# board.net
KiCad netlist of a schematic drawn in EAGLE
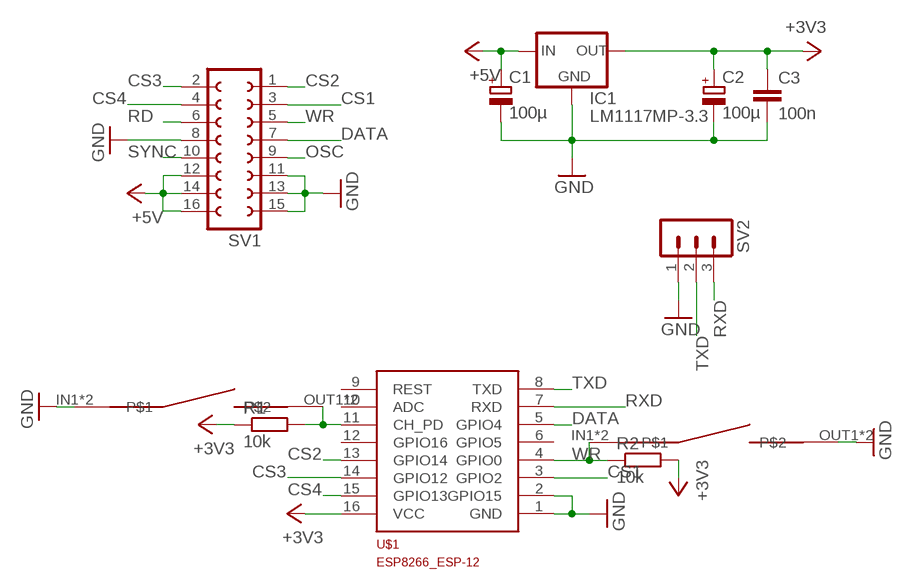
[diagram p0: schematic, sheet 1]

(export (version "E")
  (design (tool "Eeschema 10.0.6"))
  (components
    (comp (ref "C1")
      (value "100µ")
      (footprint "eagle-import:E2,5-6")
      (libsource (lib "eagle-import") (part "CPOL-EUE2.5-6"))
    )
    (comp (ref "C2")
      (value "100µ")
      (footprint "eagle-import:E2,5-6")
      (libsource (lib "eagle-import") (part "CPOL-EUE2.5-6"))
    )
    (comp (ref "C3")
      (value "100n")
      (footprint "eagle-import:C0805")
      (libsource (lib "eagle-import") (part "C-EUC0805"))
    )
    (comp (ref "IC1")
      (value "LM1117MP-3.3")
      (footprint "eagle-import:SOT223")
      (fields (field (name "MF") "Texas Instruments"))
      (libsource (lib "eagle-import") (part "LM1117?-MP3.3"))
    )
    (comp (ref "R1")
      (value "10k")
      (footprint "eagle-import:R0805")
      (libsource (lib "eagle-import") (part "R-EU_R0805"))
    )
    (comp (ref "R2")
      (value "10k")
      (footprint "eagle-import:R0805")
      (libsource (lib "eagle-import") (part "R-EU_R0805"))
    )
    (comp (ref "SV1")
      (value "FE08-2")
      (footprint "eagle-import:FE08-2")
      (libsource (lib "eagle-import") (part "FE08-2"))
    )
    (comp (ref "SV2")
      (value "MA03-1")
      (footprint "eagle-import:MA03-1")
      (libsource (lib "eagle-import") (part "MA03-1"))
    )
    (comp (ref "U$1")
      (value "ESP8266_ESP-12")
      (footprint "eagle-import:ESP8266-ESP12")
      (libsource (lib "eagle-import") (part "ESP8266_ESP-12"))
    )
    (comp (ref "U$2")
      (value "KMR221")
      (footprint "eagle-import:KMR221")
      (libsource (lib "eagle-import") (part "KMR221"))
    )
    (comp (ref "U$3")
      (value "KMR221")
      (footprint "eagle-import:KMR221")
      (libsource (lib "eagle-import") (part "KMR221"))
    )
  )
  (nets
    (net (code "1") (name "+3V3") (class "Default")
      (node (ref "C2") (pin "+") (pinfunction "+_+") (pintype "passive"))
      (node (ref "C3") (pin "1") (pinfunction "1_1") (pintype "passive"))
      (node (ref "IC1") (pin "2") (pinfunction "OUT_2") (pintype "passive"))
      (node (ref "IC1") (pin "4") (pinfunction "OUT_4") (pintype "passive"))
      (node (ref "R1") (pin "1") (pinfunction "1_1") (pintype "passive"))
      (node (ref "R2") (pin "2") (pinfunction "2_2") (pintype "passive"))
      (node (ref "U$1") (pin "16") (pinfunction "VCC_16") (pintype "bidirectional"))
    )
    (net (code "2") (name "+5V") (class "Default")
      (node (ref "C1") (pin "+") (pinfunction "+_+") (pintype "passive"))
      (node (ref "IC1") (pin "3") (pinfunction "IN_3") (pintype "input"))
      (node (ref "SV1") (pin "12") (pinfunction "12_12") (pintype "passive"))
      (node (ref "SV1") (pin "14") (pinfunction "14_14") (pintype "passive"))
      (node (ref "SV1") (pin "16") (pinfunction "16_16") (pintype "passive"))
    )
    (net (code "3") (name "/CS1") (class "Default")
      (node (ref "SV1") (pin "3") (pinfunction "3_3") (pintype "passive"))
      (node (ref "U$1") (pin "3") (pinfunction "GPIO2_3") (pintype "bidirectional"))
    )
    (net (code "4") (name "/CS2") (class "Default")
      (node (ref "SV1") (pin "1") (pinfunction "1_1") (pintype "passive"))
      (node (ref "U$1") (pin "13") (pinfunction "GPIO14_13") (pintype "bidirectional"))
    )
    (net (code "5") (name "/CS3") (class "Default")
      (node (ref "SV1") (pin "2") (pinfunction "2_2") (pintype "passive"))
      (node (ref "U$1") (pin "14") (pinfunction "GPIO12_14") (pintype "bidirectional"))
    )
    (net (code "6") (name "/CS4") (class "Default")
      (node (ref "SV1") (pin "4") (pinfunction "4_4") (pintype "passive"))
      (node (ref "U$1") (pin "15") (pinfunction "GPIO13_15") (pintype "bidirectional"))
    )
    (net (code "7") (name "/DATA") (class "Default")
      (node (ref "SV1") (pin "7") (pinfunction "7_7") (pintype "passive"))
      (node (ref "U$1") (pin "5") (pinfunction "GPIO4_5") (pintype "bidirectional"))
    )
    (net (code "8") (name "/OSC") (class "Default")
      (node (ref "SV1") (pin "9") (pinfunction "9_9") (pintype "passive"))
    )
    (net (code "9") (name "/RD") (class "Default")
      (node (ref "SV1") (pin "6") (pinfunction "6_6") (pintype "passive"))
    )
    (net (code "10") (name "/RXD") (class "Default")
      (node (ref "SV2") (pin "3") (pinfunction "3_3") (pintype "passive"))
      (node (ref "U$1") (pin "7") (pinfunction "RXD_7") (pintype "bidirectional"))
    )
    (net (code "11") (name "/SYNC") (class "Default")
      (node (ref "SV1") (pin "10") (pinfunction "10_10") (pintype "passive"))
    )
    (net (code "12") (name "/TXD") (class "Default")
      (node (ref "SV2") (pin "2") (pinfunction "2_2") (pintype "passive"))
      (node (ref "U$1") (pin "8") (pinfunction "TXD_8") (pintype "bidirectional"))
    )
    (net (code "13") (name "/WR") (class "Default")
      (node (ref "R2") (pin "1") (pinfunction "1_1") (pintype "passive"))
      (node (ref "SV1") (pin "5") (pinfunction "5_5") (pintype "passive"))
      (node (ref "U$1") (pin "4") (pinfunction "GPIO0_4") (pintype "bidirectional"))
      (node (ref "U$3") (pin "IN1") (pinfunction "P$1_IN1") (pintype "bidirectional"))
      (node (ref "U$3") (pin "IN2") (pinfunction "P$1_IN2") (pintype "bidirectional"))
    )
    (net (code "14") (name "GND") (class "Default")
      (node (ref "C1") (pin "-") (pinfunction "-_-") (pintype "passive"))
      (node (ref "C2") (pin "-") (pinfunction "-_-") (pintype "passive"))
      (node (ref "C3") (pin "2") (pinfunction "2_2") (pintype "passive"))
      (node (ref "IC1") (pin "1") (pinfunction "GND_1") (pintype "input"))
      (node (ref "SV1") (pin "11") (pinfunction "11_11") (pintype "passive"))
      (node (ref "SV1") (pin "13") (pinfunction "13_13") (pintype "passive"))
      (node (ref "SV1") (pin "15") (pinfunction "15_15") (pintype "passive"))
      (node (ref "SV1") (pin "8") (pinfunction "8_8") (pintype "passive"))
      (node (ref "SV2") (pin "1") (pinfunction "1_1") (pintype "passive"))
      (node (ref "U$1") (pin "1") (pinfunction "GND_1") (pintype "bidirectional"))
      (node (ref "U$1") (pin "2") (pinfunction "GPIO15_2") (pintype "bidirectional"))
      (node (ref "U$2") (pin "IN1") (pinfunction "P$1_IN1") (pintype "bidirectional"))
      (node (ref "U$2") (pin "IN2") (pinfunction "P$1_IN2") (pintype "bidirectional"))
      (node (ref "U$3") (pin "OUT1") (pinfunction "P$2_OUT1") (pintype "bidirectional"))
      (node (ref "U$3") (pin "OUT2") (pinfunction "P$2_OUT2") (pintype "bidirectional"))
    )
    (net (code "15") (name "Net-(U$1-CH_PD)") (class "Default")
      (node (ref "R1") (pin "2") (pinfunction "2_2") (pintype "passive"))
      (node (ref "U$1") (pin "11") (pinfunction "CH_PD_11") (pintype "bidirectional"))
      (node (ref "U$2") (pin "OUT1") (pinfunction "P$2_OUT1") (pintype "bidirectional"))
      (node (ref "U$2") (pin "OUT2") (pinfunction "P$2_OUT2") (pintype "bidirectional"))
    )
    (net (code "16") (name "unconnected-(U$1-ADC-Pad10)") (class "Default")
      (node (ref "U$1") (pin "10") (pinfunction "ADC_10") (pintype "bidirectional"))
    )
    (net (code "17") (name "unconnected-(U$1-GPIO5-Pad6)") (class "Default")
      (node (ref "U$1") (pin "6") (pinfunction "GPIO5_6") (pintype "bidirectional"))
    )
    (net (code "18") (name "unconnected-(U$1-GPIO16-Pad12)") (class "Default")
      (node (ref "U$1") (pin "12") (pinfunction "GPIO16_12") (pintype "bidirectional"))
    )
    (net (code "19") (name "unconnected-(U$1-REST-Pad9)") (class "Default")
      (node (ref "U$1") (pin "9") (pinfunction "REST_9") (pintype "bidirectional"))
    )
  )
)
